# UART.net
KiCad netlist of a schematic drawn in Altium Designer
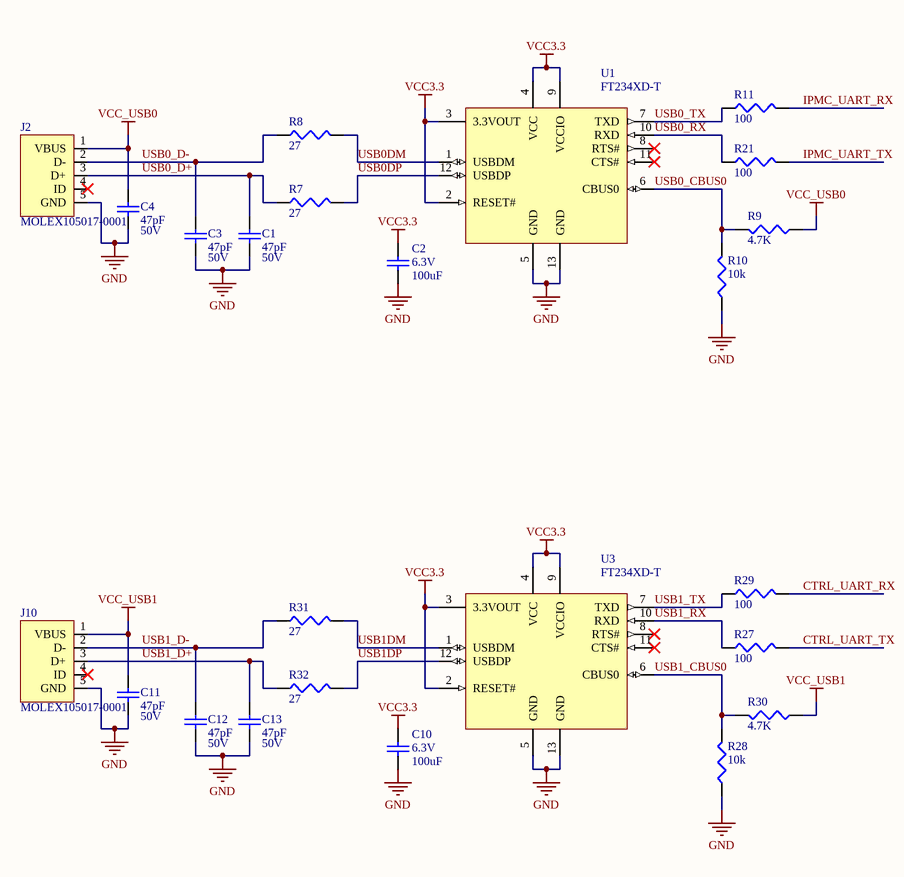
[diagram p0: UART.SchDoc]

(export (version "E")
  (design (tool "Eeschema 10.0.6"))
  (components
    (comp (ref "C1")
      (value "47pF")
      (footprint "C0402")
      (description "Capacitor (Semiconductor SIM Model)")
      (fields
        (field (name "RATING") "50V")
        (field (name "MFG. PART NO.") "CC0402JRNPO9BN470")
        (field (name "Comment") "?")
      )
      (libsource (lib "Miscellaneous Devices") (part "Cap Semi"))
    )
    (comp (ref "C2")
      (value "100uF")
      (footprint "C1210_IPC_H")
      (description "Capacitor")
      (fields
        (field (name "RATING") "6.3V")
        (field (name "MFG. PART NO.") "GRM32ER60J107ME20L")
        (field (name "Comment") "?")
      )
      (libsource (lib "CustomSymbols") (part "Cap"))
    )
    (comp (ref "C3")
      (value "47pF")
      (footprint "C0402")
      (description "Capacitor (Semiconductor SIM Model)")
      (fields
        (field (name "RATING") "50V")
        (field (name "MFG. PART NO.") "CC0402JRNPO9BN470")
        (field (name "Comment") "?")
      )
      (libsource (lib "Miscellaneous Devices") (part "Cap Semi"))
    )
    (comp (ref "C4")
      (value "47pF")
      (footprint "C0402")
      (description "Capacitor (Semiconductor SIM Model)")
      (fields
        (field (name "RATING") "50V")
        (field (name "MFG. PART NO.") "CC0402JRNPO9BN470")
        (field (name "Comment") "?")
      )
      (libsource (lib "Miscellaneous Devices") (part "Cap Semi"))
    )
    (comp (ref "C10")
      (value "100uF")
      (footprint "C1210_IPC_H")
      (description "Capacitor")
      (fields
        (field (name "RATING") "6.3V")
        (field (name "MFG. PART NO.") "GRM32ER60J107ME20L")
        (field (name "Comment") "?")
      )
      (libsource (lib "CustomSymbols") (part "Cap"))
    )
    (comp (ref "C11")
      (value "47pF")
      (footprint "C0402")
      (description "Capacitor (Semiconductor SIM Model)")
      (fields
        (field (name "RATING") "50V")
        (field (name "MFG. PART NO.") "CC0402JRNPO9BN470")
        (field (name "Comment") "?")
      )
      (libsource (lib "Miscellaneous Devices") (part "Cap Semi"))
    )
    (comp (ref "C12")
      (value "47pF")
      (footprint "C0402")
      (description "Capacitor (Semiconductor SIM Model)")
      (fields
        (field (name "RATING") "50V")
        (field (name "MFG. PART NO.") "CC0402JRNPO9BN470")
        (field (name "Comment") "?")
      )
      (libsource (lib "Miscellaneous Devices") (part "Cap Semi"))
    )
    (comp (ref "C13")
      (value "47pF")
      (footprint "C0402")
      (description "Capacitor (Semiconductor SIM Model)")
      (fields
        (field (name "RATING") "50V")
        (field (name "MFG. PART NO.") "CC0402JRNPO9BN470")
        (field (name "Comment") "?")
      )
      (libsource (lib "Miscellaneous Devices") (part "Cap Semi"))
    )
    (comp (ref "J2")
      (value "MOLEX105017-0001")
      (footprint "MOLEX105017-0001")
      (description "Micro USB Bottom Mount Receptable, B Type")
      (fields (field (name "MFG. PART NO.") "105017-0001"))
      (libsource (lib "CustomParts") (part "MOLEX105017-0001"))
    )
    (comp (ref "J10")
      (value "MOLEX105017-0001")
      (footprint "MOLEX105017-0001")
      (description "Micro USB Bottom Mount Receptable, B Type")
      (fields (field (name "MFG. PART NO.") "105017-0001"))
      (libsource (lib "CustomParts") (part "MOLEX105017-0001"))
    )
    (comp (ref "R7")
      (value "27")
      (footprint "R0603")
      (description "Resistor")
      (fields (field (name "MFG. PART NO.") "?"))
      (libsource (lib "Miscellaneous Devices") (part "Res3"))
    )
    (comp (ref "R8")
      (value "27")
      (footprint "R0603")
      (description "Resistor")
      (fields (field (name "MFG. PART NO.") "?"))
      (libsource (lib "Miscellaneous Devices") (part "Res3"))
    )
    (comp (ref "R9")
      (value "4.7K")
      (footprint "R0402_IPC_H")
      (description "Resistor")
      (fields (field (name "TOLERANCE") "5%") (field (name "MFG. PART NO.") "ERJ-2GEJ472X"))
      (libsource (lib "CustomSymbols") (part "Res"))
    )
    (comp (ref "R10")
      (value "10k")
      (footprint "R0402_IPC_H")
      (description "Resistor")
      (fields (field (name "TOLERANCE") "5%") (field (name "MFG. PART NO.") "ERJ-2GEJ103X"))
      (libsource (lib "CustomSymbols") (part "Res"))
    )
    (comp (ref "R11")
      (value "100")
      (footprint "R0603")
      (description "Resistor")
      (fields (field (name "MFG. PART NO.") "RC0603FR-07100RL") (field (name "Comment") "?"))
      (libsource (lib "Miscellaneous Devices") (part "Res3"))
    )
    (comp (ref "R21")
      (value "100")
      (footprint "R0603")
      (description "Resistor")
      (fields (field (name "MFG. PART NO.") "RC0603FR-07100RL") (field (name "Comment") "?"))
      (libsource (lib "Miscellaneous Devices") (part "Res3"))
    )
    (comp (ref "R27")
      (value "100")
      (footprint "R0603")
      (description "Resistor")
      (fields (field (name "MFG. PART NO.") "RC0603FR-07100RL") (field (name "Comment") "?"))
      (libsource (lib "Miscellaneous Devices") (part "Res3"))
    )
    (comp (ref "R28")
      (value "10k")
      (footprint "R0402_IPC_H")
      (description "Resistor")
      (fields (field (name "TOLERANCE") "5%") (field (name "MFG. PART NO.") "ERJ-2GEJ103X"))
      (libsource (lib "CustomSymbols") (part "Res"))
    )
    (comp (ref "R29")
      (value "100")
      (footprint "R0603")
      (description "Resistor")
      (fields (field (name "MFG. PART NO.") "RC0603FR-07100RL") (field (name "Comment") "?"))
      (libsource (lib "Miscellaneous Devices") (part "Res3"))
    )
    (comp (ref "R30")
      (value "4.7K")
      (footprint "R0402_IPC_H")
      (description "Resistor")
      (fields (field (name "TOLERANCE") "5%") (field (name "MFG. PART NO.") "ERJ-2GEJ472X"))
      (libsource (lib "CustomSymbols") (part "Res"))
    )
    (comp (ref "R31")
      (value "27")
      (footprint "R0603")
      (description "Resistor")
      (fields (field (name "MFG. PART NO.") "?"))
      (libsource (lib "Miscellaneous Devices") (part "Res3"))
    )
    (comp (ref "R32")
      (value "27")
      (footprint "R0603")
      (description "Resistor")
      (fields (field (name "MFG. PART NO.") "?"))
      (libsource (lib "Miscellaneous Devices") (part "Res3"))
    )
    (comp (ref "U1")
      (value "FT234XD-T")
      (footprint "DFN-12_V")
      (description "FT234XD USB to BASIC UART IC, -40 to +85 degC, 12-Pin DFN, Pb-Free, Tray")
      (fields (field (name "MFG. PART NO.") "?"))
      (libsource (lib "Altium Content Vault") (part "CMP-0248-00028-1"))
    )
    (comp (ref "U3")
      (value "FT234XD-T")
      (footprint "DFN-12_V")
      (description "FT234XD USB to BASIC UART IC, -40 to +85 degC, 12-Pin DFN, Pb-Free, Tray")
      (fields (field (name "MFG. PART NO.") "?"))
      (libsource (lib "Altium Content Vault") (part "CMP-0248-00028-1"))
    )
  )
  (nets
    (net (code "1") (name "/CTRL_UART_RX") (class "Default")
      (node (ref "R29") (pin "2") (pinfunction "2_2") (pintype "passive"))
    )
    (net (code "2") (name "/CTRL_UART_TX") (class "Default")
      (node (ref "R27") (pin "2") (pinfunction "2_2") (pintype "passive"))
    )
    (net (code "3") (name "/IPMC_UART_RX") (class "Default")
      (node (ref "R11") (pin "2") (pinfunction "2_2") (pintype "passive"))
    )
    (net (code "4") (name "/IPMC_UART_TX") (class "Default")
      (node (ref "R21") (pin "2") (pinfunction "2_2") (pintype "passive"))
    )
    (net (code "5") (name "/USB0DM") (class "Default")
      (node (ref "R8") (pin "2") (pinfunction "2_2") (pintype "passive"))
      (node (ref "U1") (pin "1") (pinfunction "USBDM_1") (pintype "bidirectional"))
    )
    (net (code "6") (name "/USB0DP") (class "Default")
      (node (ref "R7") (pin "2") (pinfunction "2_2") (pintype "passive"))
      (node (ref "U1") (pin "12") (pinfunction "USBDP_12") (pintype "bidirectional"))
    )
    (net (code "7") (name "/USB0_CBUS0") (class "Default")
      (node (ref "R10") (pin "2") (pinfunction "2_2") (pintype "passive"))
      (node (ref "R9") (pin "2") (pinfunction "2_2") (pintype "passive"))
      (node (ref "U1") (pin "6") (pinfunction "CBUS0_6") (pintype "bidirectional"))
    )
    (net (code "8") (name "/USB0_D+") (class "Default")
      (node (ref "C1") (pin "2") (pinfunction "2_2") (pintype "passive"))
      (node (ref "J2") (pin "3") (pinfunction "D+_3") (pintype "passive"))
      (node (ref "R7") (pin "1") (pinfunction "1_1") (pintype "passive"))
    )
    (net (code "9") (name "/USB0_D-") (class "Default")
      (node (ref "C3") (pin "2") (pinfunction "2_2") (pintype "passive"))
      (node (ref "J2") (pin "2") (pinfunction "D-_2") (pintype "passive"))
      (node (ref "R8") (pin "1") (pinfunction "1_1") (pintype "passive"))
    )
    (net (code "10") (name "/USB0_RX") (class "Default")
      (node (ref "R21") (pin "1") (pinfunction "1_1") (pintype "passive"))
      (node (ref "U1") (pin "10") (pinfunction "RXD_10") (pintype "input"))
    )
    (net (code "11") (name "/USB0_TX") (class "Default")
      (node (ref "R11") (pin "1") (pinfunction "1_1") (pintype "passive"))
      (node (ref "U1") (pin "7") (pinfunction "TXD_7") (pintype "output"))
    )
    (net (code "12") (name "/USB1DM") (class "Default")
      (node (ref "R31") (pin "2") (pinfunction "2_2") (pintype "passive"))
      (node (ref "U3") (pin "1") (pinfunction "USBDM_1") (pintype "bidirectional"))
    )
    (net (code "13") (name "/USB1DP") (class "Default")
      (node (ref "R32") (pin "2") (pinfunction "2_2") (pintype "passive"))
      (node (ref "U3") (pin "12") (pinfunction "USBDP_12") (pintype "bidirectional"))
    )
    (net (code "14") (name "/USB1_CBUS0") (class "Default")
      (node (ref "R28") (pin "2") (pinfunction "2_2") (pintype "passive"))
      (node (ref "R30") (pin "2") (pinfunction "2_2") (pintype "passive"))
      (node (ref "U3") (pin "6") (pinfunction "CBUS0_6") (pintype "bidirectional"))
    )
    (net (code "15") (name "/USB1_D+") (class "Default")
      (node (ref "C13") (pin "2") (pinfunction "2_2") (pintype "passive"))
      (node (ref "J10") (pin "3") (pinfunction "D+_3") (pintype "passive"))
      (node (ref "R32") (pin "1") (pinfunction "1_1") (pintype "passive"))
    )
    (net (code "16") (name "/USB1_D-") (class "Default")
      (node (ref "C12") (pin "2") (pinfunction "2_2") (pintype "passive"))
      (node (ref "J10") (pin "2") (pinfunction "D-_2") (pintype "passive"))
      (node (ref "R31") (pin "1") (pinfunction "1_1") (pintype "passive"))
    )
    (net (code "17") (name "/USB1_RX") (class "Default")
      (node (ref "R27") (pin "1") (pinfunction "1_1") (pintype "passive"))
      (node (ref "U3") (pin "10") (pinfunction "RXD_10") (pintype "input"))
    )
    (net (code "18") (name "/USB1_TX") (class "Default")
      (node (ref "R29") (pin "1") (pinfunction "1_1") (pintype "passive"))
      (node (ref "U3") (pin "7") (pinfunction "TXD_7") (pintype "output"))
    )
    (net (code "19") (name "GND") (class "Default")
      (node (ref "C1") (pin "1") (pinfunction "1_1") (pintype "passive"))
      (node (ref "C10") (pin "1") (pinfunction "1_1") (pintype "passive"))
      (node (ref "C11") (pin "1") (pinfunction "1_1") (pintype "passive"))
      (node (ref "C12") (pin "1") (pinfunction "1_1") (pintype "passive"))
      (node (ref "C13") (pin "1") (pinfunction "1_1") (pintype "passive"))
      (node (ref "C2") (pin "1") (pinfunction "1_1") (pintype "passive"))
      (node (ref "C3") (pin "1") (pinfunction "1_1") (pintype "passive"))
      (node (ref "C4") (pin "1") (pinfunction "1_1") (pintype "passive"))
      (node (ref "J10") (pin "5") (pinfunction "GND_5") (pintype "passive"))
      (node (ref "J2") (pin "5") (pinfunction "GND_5") (pintype "passive"))
      (node (ref "R10") (pin "1") (pinfunction "1_1") (pintype "passive"))
      (node (ref "R28") (pin "1") (pinfunction "1_1") (pintype "passive"))
      (node (ref "U1") (pin "13") (pinfunction "GND_13") (pintype "power_in"))
      (node (ref "U1") (pin "5") (pinfunction "GND_5") (pintype "power_in"))
      (node (ref "U3") (pin "13") (pinfunction "GND_13") (pintype "power_in"))
      (node (ref "U3") (pin "5") (pinfunction "GND_5") (pintype "power_in"))
    )
    (net (code "20") (name "VCC3.3") (class "Default")
      (node (ref "C10") (pin "2") (pinfunction "2_2") (pintype "passive"))
      (node (ref "C2") (pin "2") (pinfunction "2_2") (pintype "passive"))
      (node (ref "U1") (pin "2") (pinfunction "RESET#_2") (pintype "input"))
      (node (ref "U1") (pin "3") (pinfunction "3.3VOUT_3") (pintype "power_in"))
      (node (ref "U1") (pin "4") (pinfunction "VCC_4") (pintype "power_in"))
      (node (ref "U1") (pin "9") (pinfunction "VCCIO_9") (pintype "power_in"))
      (node (ref "U3") (pin "2") (pinfunction "RESET#_2") (pintype "input"))
      (node (ref "U3") (pin "3") (pinfunction "3.3VOUT_3") (pintype "power_in"))
      (node (ref "U3") (pin "4") (pinfunction "VCC_4") (pintype "power_in"))
      (node (ref "U3") (pin "9") (pinfunction "VCCIO_9") (pintype "power_in"))
    )
    (net (code "21") (name "VCC_USB0") (class "Default")
      (node (ref "C4") (pin "2") (pinfunction "2_2") (pintype "passive"))
      (node (ref "J2") (pin "1") (pinfunction "VBUS_1") (pintype "passive"))
      (node (ref "R9") (pin "1") (pinfunction "1_1") (pintype "passive"))
    )
    (net (code "22") (name "VCC_USB1") (class "Default")
      (node (ref "C11") (pin "2") (pinfunction "2_2") (pintype "passive"))
      (node (ref "J10") (pin "1") (pinfunction "VBUS_1") (pintype "passive"))
      (node (ref "R30") (pin "1") (pinfunction "1_1") (pintype "passive"))
    )
    (net (code "23") (name "unconnected-(J2-ID-Pad4)") (class "Default")
      (node (ref "J2") (pin "4") (pinfunction "ID_4") (pintype "passive+no_connect"))
    )
    (net (code "24") (name "unconnected-(J10-ID-Pad4)") (class "Default")
      (node (ref "J10") (pin "4") (pinfunction "ID_4") (pintype "passive+no_connect"))
    )
    (net (code "25") (name "unconnected-(U1-CTS#-Pad11)") (class "Default")
      (node (ref "U1") (pin "11") (pinfunction "CTS#_11") (pintype "input+no_connect"))
    )
    (net (code "26") (name "unconnected-(U1-RTS#-Pad8)") (class "Default")
      (node (ref "U1") (pin "8") (pinfunction "RTS#_8") (pintype "output+no_connect"))
    )
    (net (code "27") (name "unconnected-(U3-CTS#-Pad11)") (class "Default")
      (node (ref "U3") (pin "11") (pinfunction "CTS#_11") (pintype "input+no_connect"))
    )
    (net (code "28") (name "unconnected-(U3-RTS#-Pad8)") (class "Default")
      (node (ref "U3") (pin "8") (pinfunction "RTS#_8") (pintype "output+no_connect"))
    )
  )
)
